# PSM_components.net
KiCad netlist of a schematic drawn in Altium Designer
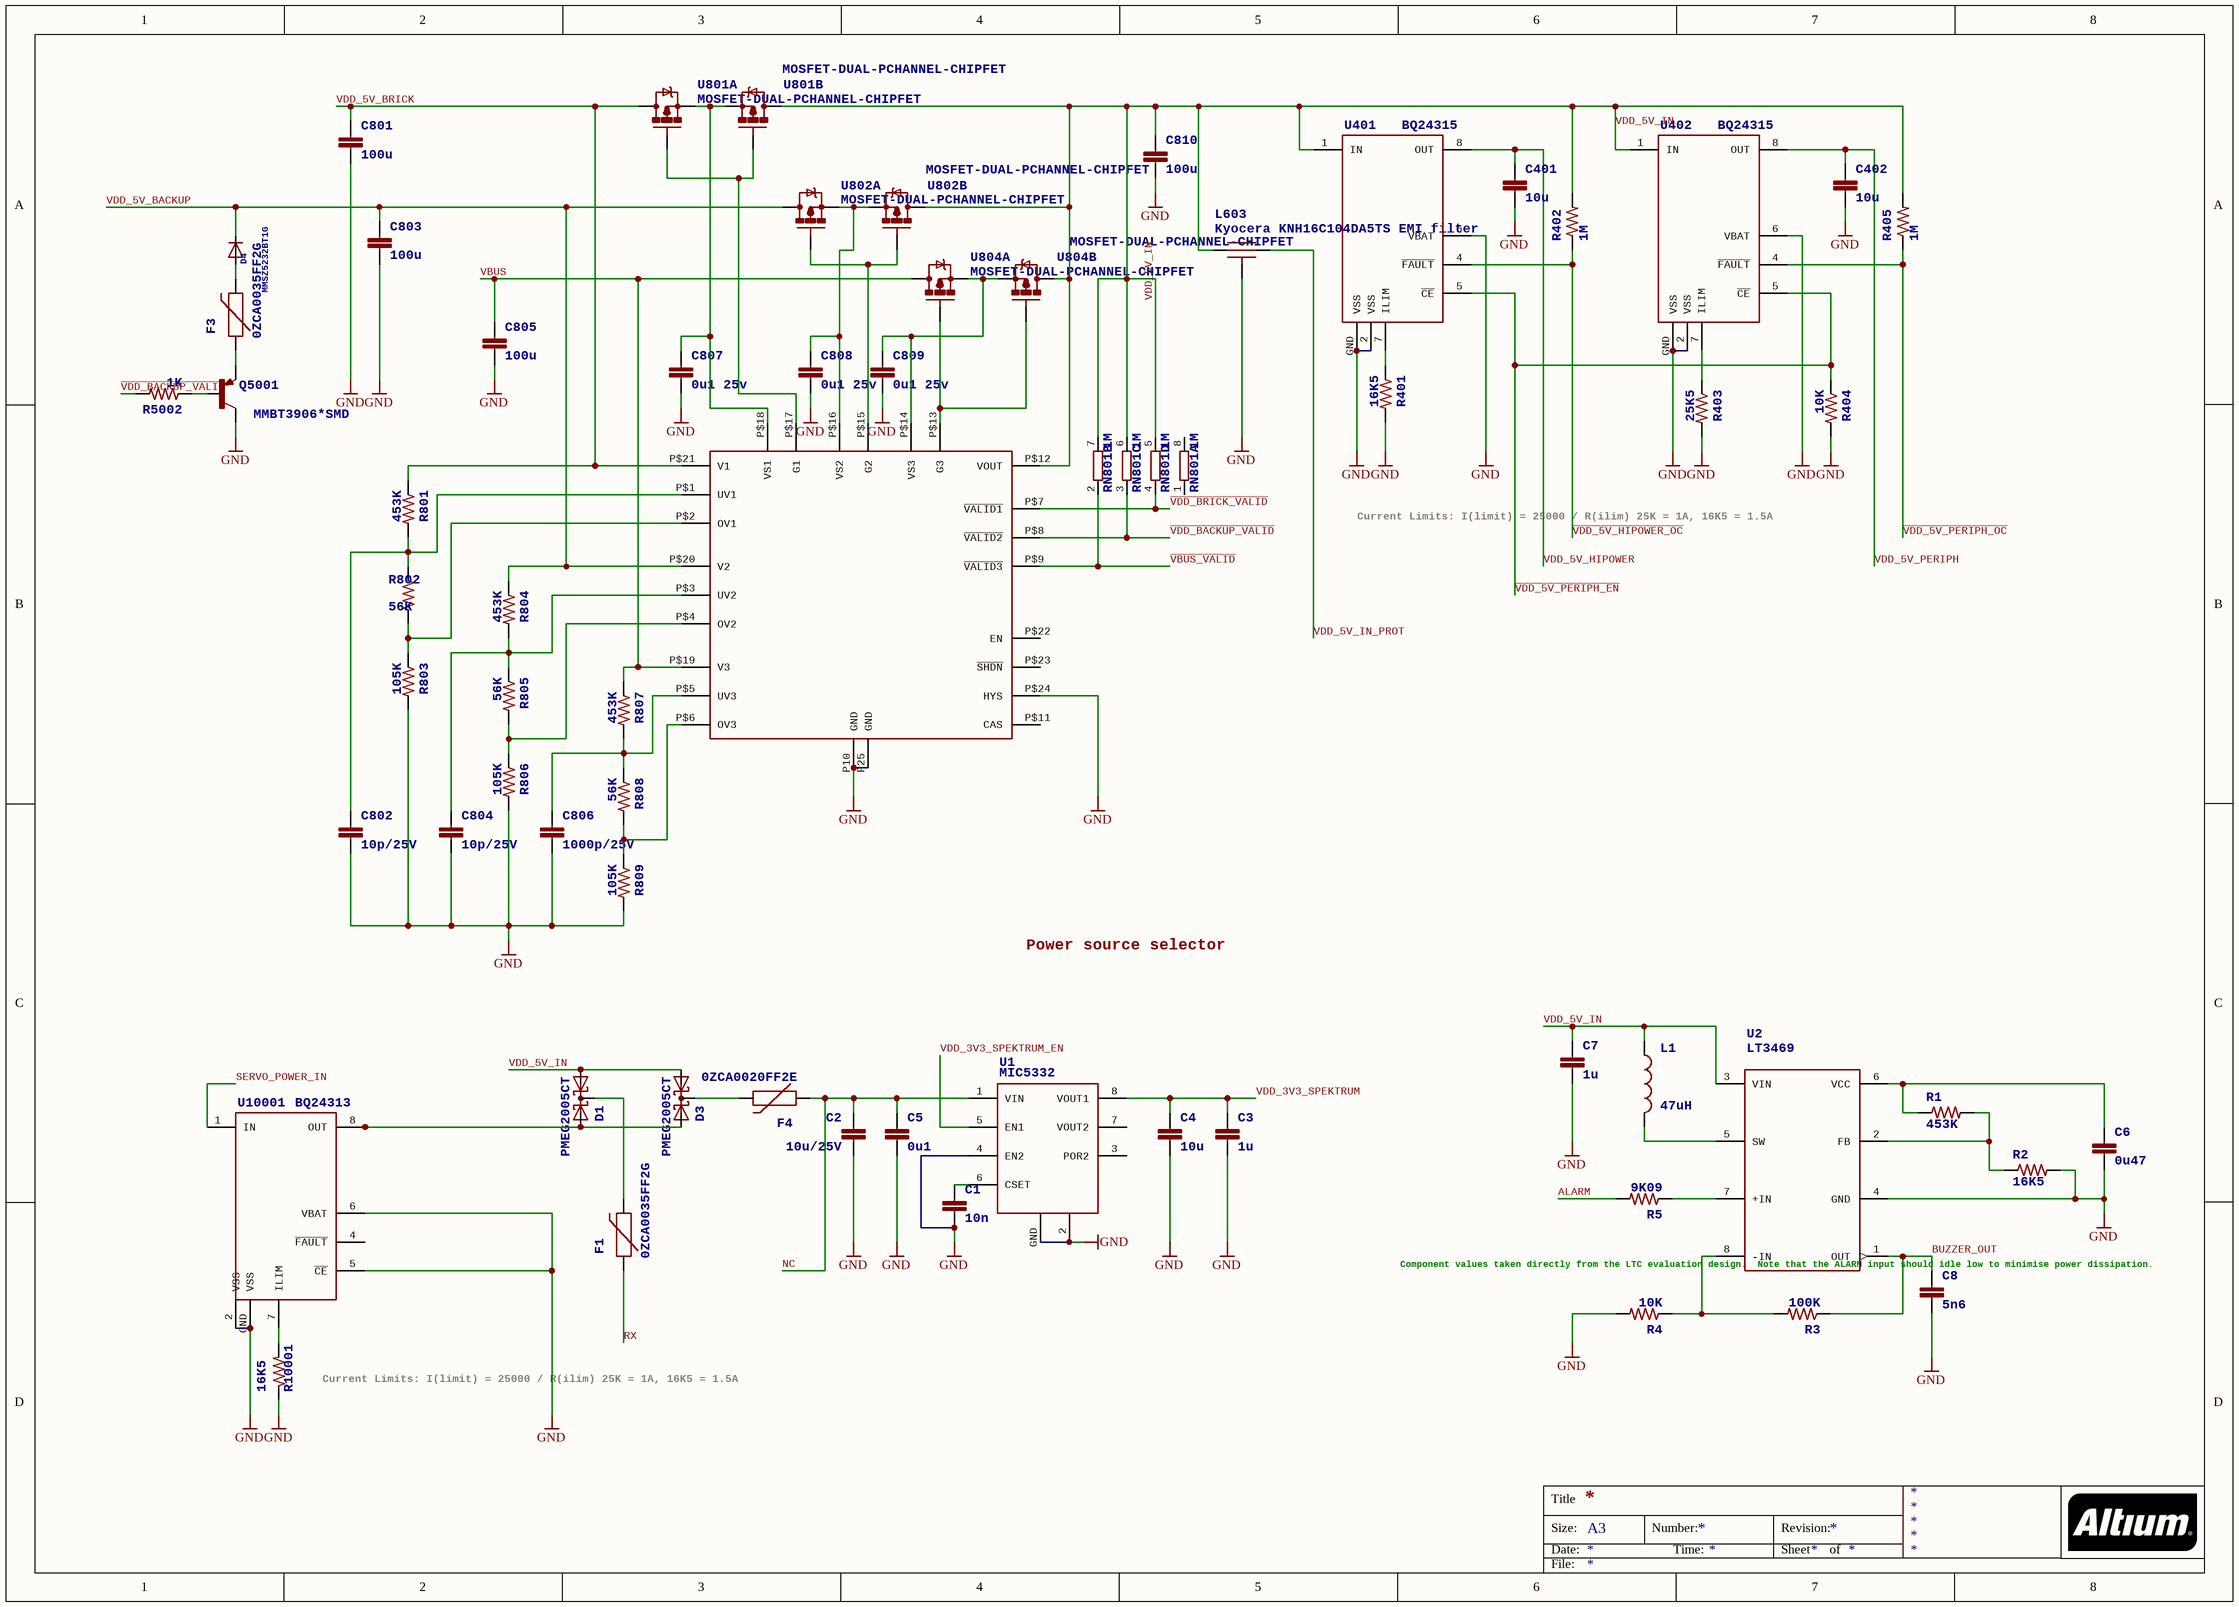
[diagram p0: PSM_components.SchDoc]

(export (version "E")
  (design (tool "Eeschema 10.0.6"))
  (components
    (comp (ref "C1") (value "10n") (footprint "PSM:0402-CAP") (libsource (lib "PSM_REV_C") (part "CAP0402")))
    (comp (ref "C2")
      (value "10u/25V")
      (footprint "PSM:0805-CAP")
      (libsource (lib "PSM_REV_C") (part "CAP0805"))
    )
    (comp (ref "C3") (value "1u") (footprint "PSM:0603-CAP") (libsource (lib "PSM_REV_C") (part "CAP0603")))
    (comp (ref "C4") (value "10u") (footprint "PSM:0603-CAP") (libsource (lib "PSM_REV_C") (part "CAP0603")))
    (comp (ref "C5") (value "0u1") (footprint "PSM:0402-CAP") (libsource (lib "PSM_REV_C") (part "CAP0402")))
    (comp (ref "C6") (value "0u47") (footprint "PSM:0402-CAP") (libsource (lib "PSM_REV_C") (part "CAP0402")))
    (comp (ref "C7") (value "1u") (footprint "PSM:0603-CAP") (libsource (lib "PSM_REV_C") (part "CAP0603")))
    (comp (ref "C8") (value "5n6") (footprint "PSM:0402-CAP") (libsource (lib "PSM_REV_C") (part "CAP0402")))
    (comp (ref "C401")
      (value "10u")
      (footprint "PSM:0603-CAP")
      (libsource (lib "PSM_REV_C") (part "CAP0603"))
    )
    (comp (ref "C402")
      (value "10u")
      (footprint "PSM:0603-CAP")
      (libsource (lib "PSM_REV_C") (part "CAP0603"))
    )
    (comp (ref "C801")
      (value "100u")
      (footprint "PSM:1206-CAP")
      (libsource (lib "PSM_REV_C") (part "CAP1206"))
    )
    (comp (ref "C802")
      (value "10p/25V")
      (footprint "PSM:0402-CAP")
      (libsource (lib "PSM_REV_C") (part "CAP0402"))
    )
    (comp (ref "C803")
      (value "100u")
      (footprint "PSM:1206-CAP")
      (libsource (lib "PSM_REV_C") (part "CAP1206"))
    )
    (comp (ref "C804")
      (value "10p/25V")
      (footprint "PSM:0402-CAP")
      (libsource (lib "PSM_REV_C") (part "CAP0402"))
    )
    (comp (ref "C805")
      (value "100u")
      (footprint "PSM:1206-CAP")
      (libsource (lib "PSM_REV_C") (part "CAP1206"))
    )
    (comp (ref "C806")
      (value "1000p/25V")
      (footprint "PSM:0402-CAP")
      (libsource (lib "PSM_REV_C") (part "CAP0402"))
    )
    (comp (ref "C807")
      (value "0u1 25v")
      (footprint "PSM:0402-CAP")
      (libsource (lib "PSM_REV_C") (part "CAP0402"))
    )
    (comp (ref "C808")
      (value "0u1 25v")
      (footprint "PSM:0402-CAP")
      (libsource (lib "PSM_REV_C") (part "CAP0402"))
    )
    (comp (ref "C809")
      (value "0u1 25v")
      (footprint "PSM:0402-CAP")
      (libsource (lib "PSM_REV_C") (part "CAP0402"))
    )
    (comp (ref "C810")
      (value "100u")
      (footprint "PSM:1206-CAP")
      (libsource (lib "PSM_REV_C") (part "CAP1206"))
    )
    (comp (ref "D1")
      (value "PMEG2005CT")
      (footprint "PSM:SOT23-3")
      (libsource (lib "PSM_REV_C") (part "PMEG2005CT"))
    )
    (comp (ref "D3")
      (value "PMEG2005CT")
      (footprint "PSM:SOT23-3")
      (libsource (lib "PSM_REV_C") (part "PMEG2005CT"))
    )
    (comp (ref "D4")
      (value "MMSZ5232BT1G")
      (footprint "PSM:SOD-123")
      (libsource (lib "PSM_REV_C") (part "DIODESOD-123"))
    )
    (comp (ref "F1")
      (value "0ZCA0035FF2G")
      (footprint "PSM:PTC-1206")
      (libsource (lib "PSM_REV_C") (part "PTCSMD"))
    )
    (comp (ref "F3")
      (value "0ZCA0035FF2G")
      (footprint "PSM:PTC-1206")
      (libsource (lib "PSM") (part "PTCSMD"))
    )
    (comp (ref "F4")
      (value "0ZCA0020FF2E")
      (footprint "PSM:PTC-1206")
      (libsource (lib "PSM_REV_C") (part "PTCSMD"))
    )
    (comp (ref "L1")
      (value "47uH")
      (footprint "PSM:0805-IND")
      (libsource (lib "PSM_REV_C") (part "INDUCTOR0805"))
    )
    (comp (ref "L603")
      (value "Kyocera KNH16C104DA5TS EMI filter")
      (footprint "PSM:KYOCERA-KNH16-DA")
      (libsource (lib "PSM_REV_C") (part "KNH16C104DA5TS"))
    )
    (comp (ref "Q5001")
      (value "MMBT3906*SMD")
      (footprint "PSM:SOT23-BEC")
      (libsource (lib "PSM_REV_C") (part "MMBT3906*SMD"))
    )
    (comp (ref "R1")
      (value "453K")
      (footprint "PSM:0402-RES")
      (libsource (lib "PSM_REV_C") (part "RESISTOR0402-RES"))
    )
    (comp (ref "R2")
      (value "16K5")
      (footprint "PSM:0402-RES")
      (libsource (lib "PSM_REV_C") (part "RESISTOR0402-RES"))
    )
    (comp (ref "R3")
      (value "100K")
      (footprint "PSM:0402-RES")
      (libsource (lib "PSM_REV_C") (part "RESISTOR0402-RES"))
    )
    (comp (ref "R4")
      (value "10K")
      (footprint "PSM:0402-RES")
      (libsource (lib "PSM_REV_C") (part "RESISTOR0402-RES"))
    )
    (comp (ref "R5")
      (value "9K09")
      (footprint "PSM:0402-RES")
      (libsource (lib "PSM_REV_C") (part "RESISTOR0402-RES"))
    )
    (comp (ref "R401")
      (value "16K5")
      (footprint "PSM:0402-RES")
      (libsource (lib "altium-import") (part "root_3_RESISTOR0402-RES_"))
    )
    (comp (ref "R402")
      (value "1M")
      (footprint "PSM:0402-RES")
      (libsource (lib "PSM_REV_C") (part "RESISTOR0402-RES"))
    )
    (comp (ref "R403")
      (value "25K5")
      (footprint "PSM:0402-RES")
      (libsource (lib "PSM_REV_C") (part "RESISTOR0402-RES"))
    )
    (comp (ref "R404")
      (value "10K")
      (footprint "PSM:0402-RES")
      (libsource (lib "PSM_REV_C") (part "RESISTOR0402-RES"))
    )
    (comp (ref "R405")
      (value "1M")
      (footprint "PSM:0402-RES")
      (libsource (lib "PSM_REV_C") (part "RESISTOR0402-RES"))
    )
    (comp (ref "R801")
      (value "453K")
      (footprint "PSM:0402-RES")
      (libsource (lib "PSM_REV_C") (part "RESISTOR0402-RES"))
    )
    (comp (ref "R802")
      (value "56K")
      (footprint "PSM:0402-RES")
      (libsource (lib "PSM_REV_C") (part "RESISTOR0402-RES_1"))
    )
    (comp (ref "R803")
      (value "105K")
      (footprint "PSM:0402-RES")
      (libsource (lib "PSM_REV_C") (part "RESISTOR0402-RES"))
    )
    (comp (ref "R804")
      (value "453K")
      (footprint "PSM:0402-RES")
      (libsource (lib "PSM_REV_C") (part "RESISTOR0402-RES"))
    )
    (comp (ref "R805")
      (value "56K")
      (footprint "PSM:0402-RES")
      (libsource (lib "PSM_REV_C") (part "RESISTOR0402-RES"))
    )
    (comp (ref "R806")
      (value "105K")
      (footprint "PSM:0402-RES")
      (libsource (lib "PSM_REV_C") (part "RESISTOR0402-RES"))
    )
    (comp (ref "R807")
      (value "453K")
      (footprint "PSM:0402-RES")
      (libsource (lib "PSM_REV_C") (part "RESISTOR0402-RES"))
    )
    (comp (ref "R808")
      (value "56K")
      (footprint "PSM:0402-RES")
      (libsource (lib "PSM_REV_C") (part "RESISTOR0402-RES"))
    )
    (comp (ref "R809")
      (value "105K")
      (footprint "PSM:0402-RES")
      (libsource (lib "PSM_REV_C") (part "RESISTOR0402-RES"))
    )
    (comp (ref "R5002")
      (value "1K")
      (footprint "PSM:0402-RES")
      (libsource (lib "PSM_REV_C") (part "RESISTOR0402-RES"))
    )
    (comp (ref "R10001")
      (value "16K5")
      (footprint "PSM:0402-RES")
      (libsource (lib "PSM_REV_C") (part "RESISTOR0402-RES"))
    )
    (comp (ref "RN801")
      (value "1M")
      (footprint "EXB28V")
      (description "RES ARRAY 1M OHM 4 RES 0804")
      (libsource (lib "PSM_REV_C") (part "4R-NEXB28V"))
    )
    (comp (ref "U1")
      (value "MIC5332")
      (footprint "PSM:MLF-8-EPAD")
      (libsource (lib "PSM_REV_C") (part "MIC5332"))
    )
    (comp (ref "U2") (value "LT3469") (footprint "PSM:SOT23-8") (libsource (lib "PSM_REV_C") (part "LT3469")))
    (comp (ref "U401")
      (value "BQ24315")
      (footprint "QFN8-DSG")
      (libsource (lib "PSM_REV_C") (part "BQ24315"))
    )
    (comp (ref "U402")
      (value "BQ24315")
      (footprint "QFN8-DSG")
      (libsource (lib "PSM_REV_C") (part "BQ24315"))
    )
    (comp (ref "U801")
      (value "MOSFET-DUAL-PCHANNEL-CHIPFET")
      (footprint "PSM:1206-8")
      (description "MOSFET 2P-CH 20V 2.9A CHIPFET")
      (libsource (lib "PSM_REV_C") (part "MOSFET-DUAL-PCHANNEL-CHIPFET"))
    )
    (comp (ref "U802")
      (value "MOSFET-DUAL-PCHANNEL-CHIPFET")
      (footprint "PSM:1206-8")
      (description "MOSFET 2P-CH 20V 2.9A CHIPFET")
      (libsource (lib "PSM_REV_C") (part "MOSFET-DUAL-PCHANNEL-CHIPFET"))
    )
    (comp (ref "U803")
      (value "LTC4417")
      (footprint "PSM:MO-220")
      (libsource (lib "altium-import") (part "root_0_LTC4117_"))
    )
    (comp (ref "U804")
      (value "MOSFET-DUAL-PCHANNEL-CHIPFET")
      (footprint "PSM:1206-8")
      (description "MOSFET 2P-CH 20V 2.9A CHIPFET")
      (libsource (lib "PSM_REV_C") (part "MOSFET-DUAL-PCHANNEL-CHIPFET"))
    )
    (comp (ref "U10001")
      (value "BQ24313")
      (footprint "QFN8-DSG")
      (libsource (lib "PSM_REV_C") (part "BQ24313"))
    )
  )
  (nets
    (net (code "1") (name "/ALARM") (class "Default")
      (node (ref "R5") (pin "P$2") (pinfunction "2_P$2") (pintype "passive"))
    )
    (net (code "2") (name "/BUZZER_OUT") (class "Default")
      (node (ref "C8") (pin "P$1") (pinfunction "1_P$1") (pintype "passive"))
      (node (ref "R3") (pin "P$1") (pinfunction "1_P$1") (pintype "passive"))
      (node (ref "U2") (pin "1") (pinfunction "OUT_1") (pintype "output"))
    )
    (net (code "3") (name "/NC") (class "Default")
      (node (ref "C2") (pin "P$1") (pinfunction "1_P$1") (pintype "passive"))
      (node (ref "C5") (pin "P$1") (pinfunction "1_P$1") (pintype "passive"))
      (node (ref "F4") (pin "1") (pinfunction "1_1") (pintype "passive"))
      (node (ref "U1") (pin "1") (pinfunction "VIN_1") (pintype "passive"))
    )
    (net (code "4") (name "/RX") (class "Default")
      (node (ref "F1") (pin "1") (pinfunction "1_1") (pintype "passive"))
    )
    (net (code "5") (name "/SERVO_POWER_IN") (class "Default")
      (node (ref "U10001") (pin "1") (pinfunction "IN_1") (pintype "passive"))
    )
    (net (code "6") (name "/VBUS") (class "Default")
      (node (ref "C805") (pin "P$1") (pinfunction "1_P$1") (pintype "passive"))
      (node (ref "R807") (pin "P$1") (pinfunction "1_P$1") (pintype "passive"))
      (node (ref "U803") (pin "P$19") (pinfunction "V3_P$19") (pintype "passive"))
      (node (ref "U804") (pin "P7") (pinfunction "D_P7") (pintype "passive"))
    )
    (net (code "7") (name "/VDD_3V3_SPEKTRUM") (class "Default")
      (node (ref "C3") (pin "P$1") (pinfunction "1_P$1") (pintype "passive"))
      (node (ref "C4") (pin "P$1") (pinfunction "1_P$1") (pintype "passive"))
      (node (ref "U1") (pin "8") (pinfunction "VOUT1_8") (pintype "passive"))
    )
    (net (code "8") (name "/VDD_3V3_SPEKTRUM_EN") (class "Default")
      (node (ref "U1") (pin "5") (pinfunction "EN1_5") (pintype "passive"))
    )
    (net (code "9") (name "/VDD_5V_BACKUP") (class "Default")
      (node (ref "C803") (pin "P$1") (pinfunction "1_P$1") (pintype "passive"))
      (node (ref "D4") (pin "C") (pinfunction "C_C") (pintype "passive"))
      (node (ref "R804") (pin "P$1") (pinfunction "1_P$1") (pintype "passive"))
      (node (ref "U802") (pin "P7") (pinfunction "D_P7") (pintype "passive"))
      (node (ref "U803") (pin "P$20") (pinfunction "V2_P$20") (pintype "passive"))
    )
    (net (code "10") (name "/VDD_5V_BRICK") (class "Default")
      (node (ref "C801") (pin "P$1") (pinfunction "1_P$1") (pintype "passive"))
      (node (ref "R801") (pin "P$1") (pinfunction "1_P$1") (pintype "passive"))
      (node (ref "U801") (pin "P7") (pinfunction "D_P7") (pintype "passive"))
      (node (ref "U803") (pin "P$21") (pinfunction "V1_P$21") (pintype "passive"))
    )
    (net (code "11") (name "/VDD_5V_HIPOWER") (class "Default")
      (node (ref "C401") (pin "P$1") (pinfunction "1_P$1") (pintype "passive"))
      (node (ref "U401") (pin "8") (pinfunction "OUT_8") (pintype "passive"))
    )
    (net (code "12") (name "/VDD_5V_IN") (class "Default")
      (node (ref "C7") (pin "P$1") (pinfunction "1_P$1") (pintype "passive"))
      (node (ref "C810") (pin "P$1") (pinfunction "1_P$1") (pintype "passive"))
      (node (ref "D1") (pin "1") (pinfunction "A1_1") (pintype "passive"))
      (node (ref "D3") (pin "1") (pinfunction "A1_1") (pintype "passive"))
      (node (ref "L1") (pin "P$1") (pinfunction "1_P$1") (pintype "passive"))
      (node (ref "L603") (pin "P$1") (pinfunction "P$1_P$1") (pintype "passive"))
      (node (ref "R402") (pin "P$2") (pinfunction "2_P$2") (pintype "passive"))
      (node (ref "R405") (pin "P$2") (pinfunction "2_P$2") (pintype "passive"))
      (node (ref "RN801") (pin "5") (pinfunction "2_5") (pintype "passive"))
      (node (ref "RN801") (pin "6") (pinfunction "2_6") (pintype "passive"))
      (node (ref "RN801") (pin "7") (pinfunction "2_7") (pintype "passive"))
      (node (ref "U2") (pin "3") (pinfunction "VIN_3") (pintype "power_in"))
      (node (ref "U401") (pin "1") (pinfunction "IN_1") (pintype "passive"))
      (node (ref "U402") (pin "1") (pinfunction "IN_1") (pintype "passive"))
      (node (ref "U801") (pin "P5") (pinfunction "D_P5") (pintype "passive"))
      (node (ref "U802") (pin "P5") (pinfunction "D_P5") (pintype "passive"))
      (node (ref "U803") (pin "P$12") (pinfunction "VOUT_P$12") (pintype "passive"))
      (node (ref "U804") (pin "P5") (pinfunction "D_P5") (pintype "passive"))
    )
    (net (code "13") (name "/VDD_5V_IN_PROT") (class "Default")
      (node (ref "L603") (pin "P$2") (pinfunction "P$2_P$2") (pintype "passive"))
    )
    (net (code "14") (name "/VDD_5V_PERIPH") (class "Default")
      (node (ref "C402") (pin "P$1") (pinfunction "1_P$1") (pintype "passive"))
      (node (ref "U402") (pin "8") (pinfunction "OUT_8") (pintype "passive"))
    )
    (net (code "15") (name "/~{VBUS_VALID}") (class "Default")
      (node (ref "RN801") (pin "2") (pinfunction "1_2") (pintype "passive"))
      (node (ref "U803") (pin "P$9") (pinfunction "~{VALID3}_P$9") (pintype "passive"))
    )
    (net (code "16") (name "/~{VDD_5V_HIPOWER_OC}") (class "Default")
      (node (ref "R402") (pin "P$1") (pinfunction "1_P$1") (pintype "passive"))
      (node (ref "U401") (pin "4") (pinfunction "~{FAULT}_4") (pintype "passive"))
    )
    (net (code "17") (name "/~{VDD_5V_PERIPH_EN}") (class "Default")
      (node (ref "R404") (pin "P$1") (pinfunction "1_P$1") (pintype "passive"))
      (node (ref "U401") (pin "5") (pinfunction "~{CE}_5") (pintype "passive"))
      (node (ref "U402") (pin "5") (pinfunction "~{CE}_5") (pintype "passive"))
    )
    (net (code "18") (name "/~{VDD_5V_PERIPH_OC}") (class "Default")
      (node (ref "R405") (pin "P$1") (pinfunction "1_P$1") (pintype "passive"))
      (node (ref "U402") (pin "4") (pinfunction "~{FAULT}_4") (pintype "passive"))
    )
    (net (code "19") (name "/~{VDD_BACKUP_VALID}") (class "Default")
      (node (ref "R5002") (pin "P$2") (pinfunction "2_P$2") (pintype "passive"))
      (node (ref "RN801") (pin "3") (pinfunction "1_3") (pintype "passive"))
      (node (ref "U803") (pin "P$8") (pinfunction "~{VALID2}_P$8") (pintype "passive"))
    )
    (net (code "20") (name "/~{VDD_BRICK_VALID}") (class "Default")
      (node (ref "RN801") (pin "4") (pinfunction "1_4") (pintype "passive"))
      (node (ref "U803") (pin "P$7") (pinfunction "~{VALID1}_P$7") (pintype "passive"))
    )
    (net (code "21") (name "GND") (class "Default")
      (node (ref "C1") (pin "P$2") (pinfunction "2_P$2") (pintype "passive"))
      (node (ref "C2") (pin "P$2") (pinfunction "2_P$2") (pintype "passive"))
      (node (ref "C3") (pin "P$2") (pinfunction "2_P$2") (pintype "passive"))
      (node (ref "C4") (pin "P$2") (pinfunction "2_P$2") (pintype "passive"))
      (node (ref "C401") (pin "P$2") (pinfunction "2_P$2") (pintype "passive"))
      (node (ref "C402") (pin "P$2") (pinfunction "2_P$2") (pintype "passive"))
      (node (ref "C5") (pin "P$2") (pinfunction "2_P$2") (pintype "passive"))
      (node (ref "C6") (pin "P$2") (pinfunction "2_P$2") (pintype "passive"))
      (node (ref "C7") (pin "P$2") (pinfunction "2_P$2") (pintype "passive"))
      (node (ref "C8") (pin "P$2") (pinfunction "2_P$2") (pintype "passive"))
      (node (ref "C801") (pin "P$2") (pinfunction "2_P$2") (pintype "passive"))
      (node (ref "C802") (pin "P$2") (pinfunction "2_P$2") (pintype "passive"))
      (node (ref "C803") (pin "P$2") (pinfunction "2_P$2") (pintype "passive"))
      (node (ref "C804") (pin "P$2") (pinfunction "2_P$2") (pintype "passive"))
      (node (ref "C805") (pin "P$2") (pinfunction "2_P$2") (pintype "passive"))
      (node (ref "C806") (pin "P$2") (pinfunction "2_P$2") (pintype "passive"))
      (node (ref "C807") (pin "P$2") (pinfunction "2_P$2") (pintype "passive"))
      (node (ref "C808") (pin "P$2") (pinfunction "2_P$2") (pintype "passive"))
      (node (ref "C809") (pin "P$2") (pinfunction "2_P$2") (pintype "passive"))
      (node (ref "C810") (pin "P$2") (pinfunction "2_P$2") (pintype "passive"))
      (node (ref "L603") (pin "GND") (pinfunction "GND_GND") (pintype "passive"))
      (node (ref "Q5001") (pin "C") (pinfunction "C_C") (pintype "passive"))
      (node (ref "R10001") (pin "P$1") (pinfunction "1_P$1") (pintype "passive"))
      (node (ref "R2") (pin "P$2") (pinfunction "2_P$2") (pintype "passive"))
      (node (ref "R4") (pin "P$2") (pinfunction "2_P$2") (pintype "passive"))
      (node (ref "R401") (pin "P$2") (pinfunction "2_P$2") (pintype "passive"))
      (node (ref "R403") (pin "P$2") (pinfunction "2_P$2") (pintype "passive"))
      (node (ref "R404") (pin "P$2") (pinfunction "2_P$2") (pintype "passive"))
      (node (ref "R803") (pin "P$2") (pinfunction "2_P$2") (pintype "passive"))
      (node (ref "R806") (pin "P$2") (pinfunction "2_P$2") (pintype "passive"))
      (node (ref "R809") (pin "P$2") (pinfunction "2_P$2") (pintype "passive"))
      (node (ref "U1") (pin "2") (pinfunction "GND_2") (pintype "power_in"))
      (node (ref "U1") (pin "4") (pinfunction "EN2_4") (pintype "passive"))
      (node (ref "U1") (pin "GND") (pinfunction "GND_GND") (pintype "power_in"))
      (node (ref "U10001") (pin "2") (pinfunction "VSS_2") (pintype "passive"))
      (node (ref "U10001") (pin "5") (pinfunction "~{CE}_5") (pintype "passive"))
      (node (ref "U10001") (pin "6") (pinfunction "VBAT_6") (pintype "passive"))
      (node (ref "U10001") (pin "GND") (pinfunction "VSS_GND") (pintype "passive"))
      (node (ref "U2") (pin "4") (pinfunction "GND_4") (pintype "power_in"))
      (node (ref "U401") (pin "2") (pinfunction "VSS_2") (pintype "passive"))
      (node (ref "U401") (pin "6") (pinfunction "VBAT_6") (pintype "passive"))
      (node (ref "U401") (pin "GND") (pinfunction "VSS_GND") (pintype "passive"))
      (node (ref "U402") (pin "2") (pinfunction "VSS_2") (pintype "passive"))
      (node (ref "U402") (pin "6") (pinfunction "VBAT_6") (pintype "passive"))
      (node (ref "U402") (pin "GND") (pinfunction "VSS_GND") (pintype "passive"))
      (node (ref "U803") (pin "P$24") (pinfunction "HYS_P$24") (pintype "passive"))
      (node (ref "U803") (pin "P10") (pinfunction "GND_P10") (pintype "passive"))
      (node (ref "U803") (pin "P25") (pinfunction "GND_P25") (pintype "passive"))
    )
    (net (code "22") (name "Net-(C1-1)") (class "Default")
      (node (ref "C1") (pin "P$1") (pinfunction "1_P$1") (pintype "passive"))
      (node (ref "U1") (pin "6") (pinfunction "CSET_6") (pintype "passive"))
    )
    (net (code "23") (name "Net-(C6-1)") (class "Default")
      (node (ref "C6") (pin "P$1") (pinfunction "1_P$1") (pintype "passive"))
      (node (ref "R1") (pin "P$1") (pinfunction "1_P$1") (pintype "passive"))
      (node (ref "U2") (pin "6") (pinfunction "VCC_6") (pintype "passive"))
    )
    (net (code "24") (name "Net-(C802-1)") (class "Default")
      (node (ref "C802") (pin "P$1") (pinfunction "1_P$1") (pintype "passive"))
      (node (ref "R801") (pin "P$2") (pinfunction "2_P$2") (pintype "passive"))
      (node (ref "R802") (pin "P$1") (pinfunction "1_P$1") (pintype "passive"))
      (node (ref "U803") (pin "P$1") (pinfunction "UV1_P$1") (pintype "passive"))
    )
    (net (code "25") (name "Net-(C804-1)") (class "Default")
      (node (ref "C804") (pin "P$1") (pinfunction "1_P$1") (pintype "passive"))
      (node (ref "R804") (pin "P$2") (pinfunction "2_P$2") (pintype "passive"))
      (node (ref "R805") (pin "P$1") (pinfunction "1_P$1") (pintype "passive"))
      (node (ref "U803") (pin "P$3") (pinfunction "UV2_P$3") (pintype "passive"))
    )
    (net (code "26") (name "Net-(C806-1)") (class "Default")
      (node (ref "C806") (pin "P$1") (pinfunction "1_P$1") (pintype "passive"))
      (node (ref "R807") (pin "P$2") (pinfunction "2_P$2") (pintype "passive"))
      (node (ref "R808") (pin "P$1") (pinfunction "1_P$1") (pintype "passive"))
      (node (ref "U803") (pin "P$5") (pinfunction "UV3_P$5") (pintype "passive"))
    )
    (net (code "27") (name "Net-(C807-1)") (class "Default")
      (node (ref "C807") (pin "P$1") (pinfunction "1_P$1") (pintype "passive"))
      (node (ref "U801") (pin "P1") (pinfunction "S_P1") (pintype "passive"))
      (node (ref "U801") (pin "P3") (pinfunction "S_P3") (pintype "passive"))
      (node (ref "U803") (pin "P$18") (pinfunction "VS1_P$18") (pintype "passive"))
    )
    (net (code "28") (name "Net-(C808-1)") (class "Default")
      (node (ref "C808") (pin "P$1") (pinfunction "1_P$1") (pintype "passive"))
      (node (ref "U802") (pin "P1") (pinfunction "S_P1") (pintype "passive"))
      (node (ref "U802") (pin "P3") (pinfunction "S_P3") (pintype "passive"))
      (node (ref "U803") (pin "P$16") (pinfunction "VS2_P$16") (pintype "passive"))
    )
    (net (code "29") (name "Net-(C809-1)") (class "Default")
      (node (ref "C809") (pin "P$1") (pinfunction "1_P$1") (pintype "passive"))
      (node (ref "U803") (pin "P$14") (pinfunction "VS3_P$14") (pintype "passive"))
      (node (ref "U804") (pin "P1") (pinfunction "S_P1") (pintype "passive"))
      (node (ref "U804") (pin "P3") (pinfunction "S_P3") (pintype "passive"))
    )
    (net (code "30") (name "Net-(D1-A2)") (class "Default")
      (node (ref "D1") (pin "2") (pinfunction "A2_2") (pintype "passive"))
      (node (ref "D3") (pin "2") (pinfunction "A2_2") (pintype "passive"))
      (node (ref "U10001") (pin "8") (pinfunction "OUT_8") (pintype "passive"))
    )
    (net (code "31") (name "Net-(D1-CC)") (class "Default")
      (node (ref "D1") (pin "3") (pinfunction "CC_3") (pintype "passive"))
      (node (ref "F1") (pin "2") (pinfunction "2_2") (pintype "passive"))
    )
    (net (code "32") (name "Net-(D3-CC)") (class "Default")
      (node (ref "D3") (pin "3") (pinfunction "CC_3") (pintype "passive"))
      (node (ref "F4") (pin "2") (pinfunction "2_2") (pintype "passive"))
    )
    (net (code "33") (name "Net-(D4-PadA)") (class "Default")
      (node (ref "D4") (pin "A") (pinfunction "A_A") (pintype "passive"))
      (node (ref "F3") (pin "2") (pinfunction "2_2") (pintype "passive"))
    )
    (net (code "34") (name "Net-(F3-Pad1)") (class "Default")
      (node (ref "F3") (pin "1") (pinfunction "1_1") (pintype "passive"))
      (node (ref "Q5001") (pin "E") (pinfunction "E_E") (pintype "passive"))
    )
    (net (code "35") (name "Net-(L1-2)") (class "Default")
      (node (ref "L1") (pin "P$2") (pinfunction "2_P$2") (pintype "passive"))
      (node (ref "U2") (pin "5") (pinfunction "SW_5") (pintype "passive"))
    )
    (net (code "36") (name "Net-(R1-2)") (class "Default")
      (node (ref "R1") (pin "P$2") (pinfunction "2_P$2") (pintype "passive"))
      (node (ref "R2") (pin "P$1") (pinfunction "1_P$1") (pintype "passive"))
      (node (ref "U2") (pin "2") (pinfunction "FB_2") (pintype "passive"))
    )
    (net (code "37") (name "Net-(R3-2)") (class "Default")
      (node (ref "R3") (pin "P$2") (pinfunction "2_P$2") (pintype "passive"))
      (node (ref "R4") (pin "P$1") (pinfunction "1_P$1") (pintype "passive"))
      (node (ref "U2") (pin "8") (pinfunction "-IN_8") (pintype "passive"))
    )
    (net (code "38") (name "Net-(R5-1)") (class "Default")
      (node (ref "R5") (pin "P$1") (pinfunction "1_P$1") (pintype "passive"))
      (node (ref "U2") (pin "7") (pinfunction "+IN_7") (pintype "passive"))
    )
    (net (code "39") (name "Net-(R401-1)") (class "Default")
      (node (ref "R401") (pin "P$1") (pinfunction "1_P$1") (pintype "passive"))
      (node (ref "U401") (pin "7") (pinfunction "ILIM_7") (pintype "passive"))
    )
    (net (code "40") (name "Net-(R403-1)") (class "Default")
      (node (ref "R403") (pin "P$1") (pinfunction "1_P$1") (pintype "passive"))
      (node (ref "U402") (pin "7") (pinfunction "ILIM_7") (pintype "passive"))
    )
    (net (code "41") (name "Net-(R802-2)") (class "Default")
      (node (ref "R802") (pin "P$2") (pinfunction "2_P$2") (pintype "passive"))
      (node (ref "R803") (pin "P$1") (pinfunction "1_P$1") (pintype "passive"))
      (node (ref "U803") (pin "P$2") (pinfunction "OV1_P$2") (pintype "passive"))
    )
    (net (code "42") (name "Net-(R805-2)") (class "Default")
      (node (ref "R805") (pin "P$2") (pinfunction "2_P$2") (pintype "passive"))
      (node (ref "R806") (pin "P$1") (pinfunction "1_P$1") (pintype "passive"))
      (node (ref "U803") (pin "P$4") (pinfunction "OV2_P$4") (pintype "passive"))
    )
    (net (code "43") (name "Net-(R808-2)") (class "Default")
      (node (ref "R808") (pin "P$2") (pinfunction "2_P$2") (pintype "passive"))
      (node (ref "R809") (pin "P$1") (pinfunction "1_P$1") (pintype "passive"))
      (node (ref "U803") (pin "P$6") (pinfunction "OV3_P$6") (pintype "passive"))
    )
    (net (code "44") (name "Net-(R5002-1)") (class "Default")
      (node (ref "Q5001") (pin "B") (pinfunction "B_B") (pintype "passive"))
      (node (ref "R5002") (pin "P$1") (pinfunction "1_P$1") (pintype "passive"))
    )
    (net (code "45") (name "Net-(R10001-2)") (class "Default")
      (node (ref "R10001") (pin "P$2") (pinfunction "2_P$2") (pintype "passive"))
      (node (ref "U10001") (pin "7") (pinfunction "ILIM_7") (pintype "passive"))
    )
    (net (code "46") (name "Net-(U801A-G)") (class "Default")
      (node (ref "U801") (pin "P2") (pinfunction "G_P2") (pintype "passive"))
      (node (ref "U801") (pin "P4") (pinfunction "G_P4") (pintype "passive"))
      (node (ref "U803") (pin "P$17") (pinfunction "G1_P$17") (pintype "passive"))
    )
    (net (code "47") (name "Net-(U802A-G)") (class "Default")
      (node (ref "U802") (pin "P2") (pinfunction "G_P2") (pintype "passive"))
      (node (ref "U802") (pin "P4") (pinfunction "G_P4") (pintype "passive"))
      (node (ref "U803") (pin "P$15") (pinfunction "G2_P$15") (pintype "passive"))
    )
    (net (code "48") (name "Net-(U803-G3)") (class "Default")
      (node (ref "U803") (pin "P$13") (pinfunction "G3_P$13") (pintype "passive"))
      (node (ref "U804") (pin "P2") (pinfunction "G_P2") (pintype "passive"))
      (node (ref "U804") (pin "P4") (pinfunction "G_P4") (pintype "passive"))
    )
    (net (code "49") (name "unconnected-(RN801-Pad1)") (class "Default")
      (node (ref "RN801") (pin "1") (pinfunction "1_1") (pintype "passive"))
    )
    (net (code "50") (name "unconnected-(RN801A-2-Pad8)") (class "Default")
      (node (ref "RN801") (pin "8") (pinfunction "2_8") (pintype "passive"))
    )
    (net (code "51") (name "unconnected-(U1-POR2-Pad3)") (class "Default")
      (node (ref "U1") (pin "3") (pinfunction "POR2_3") (pintype "passive"))
    )
    (net (code "52") (name "unconnected-(U1-VOUT2-Pad7)") (class "Default")
      (node (ref "U1") (pin "7") (pinfunction "VOUT2_7") (pintype "passive"))
    )
    (net (code "53") (name "unconnected-(U803-CAS-PadP$11)") (class "Default")
      (node (ref "U803") (pin "P$11") (pinfunction "CAS_P$11") (pintype "passive"))
    )
    (net (code "54") (name "unconnected-(U803-EN-PadP$22)") (class "Default")
      (node (ref "U803") (pin "P$22") (pinfunction "EN_P$22") (pintype "passive"))
    )
    (net (code "55") (name "unconnected-(U803-~{SHDN}-PadP$23)") (class "Default")
      (node (ref "U803") (pin "P$23") (pinfunction "~{SHDN}_P$23") (pintype "passive"))
    )
    (net (code "56") (name "unconnected-(U10001-~{FAULT}-Pad4)") (class "Default")
      (node (ref "U10001") (pin "4") (pinfunction "~{FAULT}_4") (pintype "passive"))
    )
  )
)
